# IR_SENSOR_PCB_design.net
KiCad netlist of a schematic drawn in EAGLE
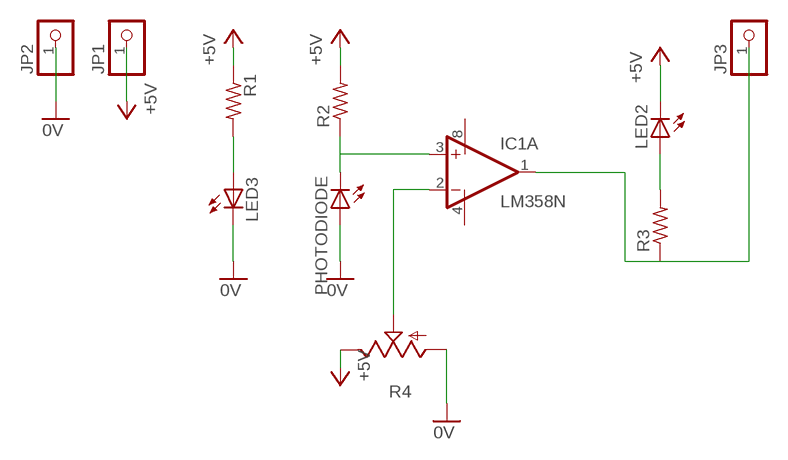
[diagram p0: schematic, sheet 1]

(export (version "E")
  (design (tool "Eeschema 10.0.6"))
  (components
    (comp (ref "IC1")
      (value "LM358N")
      (footprint "eagle-import:DIL08")
      (libsource (lib "eagle-import") (part "LM358N"))
    )
    (comp (ref "JP1")
      (value "PINHD-1X1")
      (footprint "eagle-import:1X01")
      (libsource (lib "eagle-import") (part "PINHD-1X1"))
    )
    (comp (ref "JP2")
      (value "PINHD-1X1")
      (footprint "eagle-import:1X01")
      (libsource (lib "eagle-import") (part "PINHD-1X1"))
    )
    (comp (ref "JP3")
      (value "PINHD-1X1")
      (footprint "eagle-import:1X01")
      (libsource (lib "eagle-import") (part "PINHD-1X1"))
    )
    (comp (ref "LED2")
      (value "LED3MM")
      (footprint "eagle-import:LED3MM")
      (libsource (lib "eagle-import") (part "LED3MM"))
    )
    (comp (ref "LED3")
      (value "LED3MM")
      (footprint "eagle-import:LED3MM")
      (libsource (lib "eagle-import") (part "LED3MM"))
    )
    (comp (ref "PHOTODIODE")
      (value "LED3MM")
      (footprint "eagle-import:LED3MM")
      (libsource (lib "eagle-import") (part "LED3MM"))
    )
    (comp (ref "R1")
      (value "R-US_0207/10")
      (footprint "eagle-import:0207_10")
      (libsource (lib "eagle-import") (part "R-US_0207/10"))
    )
    (comp (ref "R2")
      (value "R-US_0207/10")
      (footprint "eagle-import:0207_10")
      (libsource (lib "eagle-import") (part "R-US_0207/10"))
    )
    (comp (ref "R3")
      (value "R-US_0207/10")
      (footprint "eagle-import:0207_10")
      (libsource (lib "eagle-import") (part "R-US_0207/10"))
    )
    (comp (ref "R4")
      (value "TRIM_US-B25U")
      (footprint "eagle-import:B25U")
      (libsource (lib "eagle-import") (part "TRIM_US-B25U"))
    )
  )
  (nets
    (net (code "1") (name "+5V") (class "Default")
      (node (ref "JP1") (pin "1") (pinfunction "1_1") (pintype "passive"))
      (node (ref "LED2") (pin "K") (pinfunction "C_K") (pintype "passive"))
      (node (ref "R1") (pin "1") (pinfunction "1_1") (pintype "passive"))
      (node (ref "R2") (pin "2") (pinfunction "2_2") (pintype "passive"))
      (node (ref "R4") (pin "E") (pinfunction "E_E") (pintype "passive"))
    )
    (net (code "2") (name "/V+") (class "Default")
      (node (ref "IC1") (pin "8") (pinfunction "V+_8") (pintype "power_in"))
    )
    (net (code "3") (name "/V-") (class "Default")
      (node (ref "IC1") (pin "4") (pinfunction "V-_4") (pintype "power_in"))
    )
    (net (code "4") (name "0V") (class "Default")
      (node (ref "JP2") (pin "1") (pinfunction "1_1") (pintype "passive"))
      (node (ref "LED3") (pin "K") (pinfunction "C_K") (pintype "passive"))
      (node (ref "PHOTODIODE") (pin "A") (pinfunction "A_A") (pintype "passive"))
      (node (ref "R4") (pin "A") (pinfunction "A_A") (pintype "passive"))
    )
    (net (code "5") (name "Net-(IC1A-+IN)") (class "Default")
      (node (ref "IC1") (pin "3") (pinfunction "+IN_3") (pintype "input"))
      (node (ref "PHOTODIODE") (pin "K") (pinfunction "C_K") (pintype "passive"))
      (node (ref "R2") (pin "1") (pinfunction "1_1") (pintype "passive"))
    )
    (net (code "6") (name "Net-(IC1A--IN)") (class "Default")
      (node (ref "IC1") (pin "2") (pinfunction "-IN_2") (pintype "input"))
      (node (ref "R4") (pin "S") (pinfunction "S_S") (pintype "passive"))
    )
    (net (code "7") (name "Net-(IC1A-OUT)") (class "Default")
      (node (ref "IC1") (pin "1") (pinfunction "OUT_1") (pintype "output"))
      (node (ref "JP3") (pin "1") (pinfunction "1_1") (pintype "passive"))
      (node (ref "R3") (pin "1") (pinfunction "1_1") (pintype "passive"))
    )
    (net (code "8") (name "Net-(LED2-PadA)") (class "Default")
      (node (ref "LED2") (pin "A") (pinfunction "A_A") (pintype "passive"))
      (node (ref "R3") (pin "2") (pinfunction "2_2") (pintype "passive"))
    )
    (net (code "9") (name "Net-(LED3-PadA)") (class "Default")
      (node (ref "LED3") (pin "A") (pinfunction "A_A") (pintype "passive"))
      (node (ref "R1") (pin "2") (pinfunction "2_2") (pintype "passive"))
    )
  )
)
